# SCH_Manip_2024-04-15.net
KiCad netlist of a schematic drawn in EasyEDA
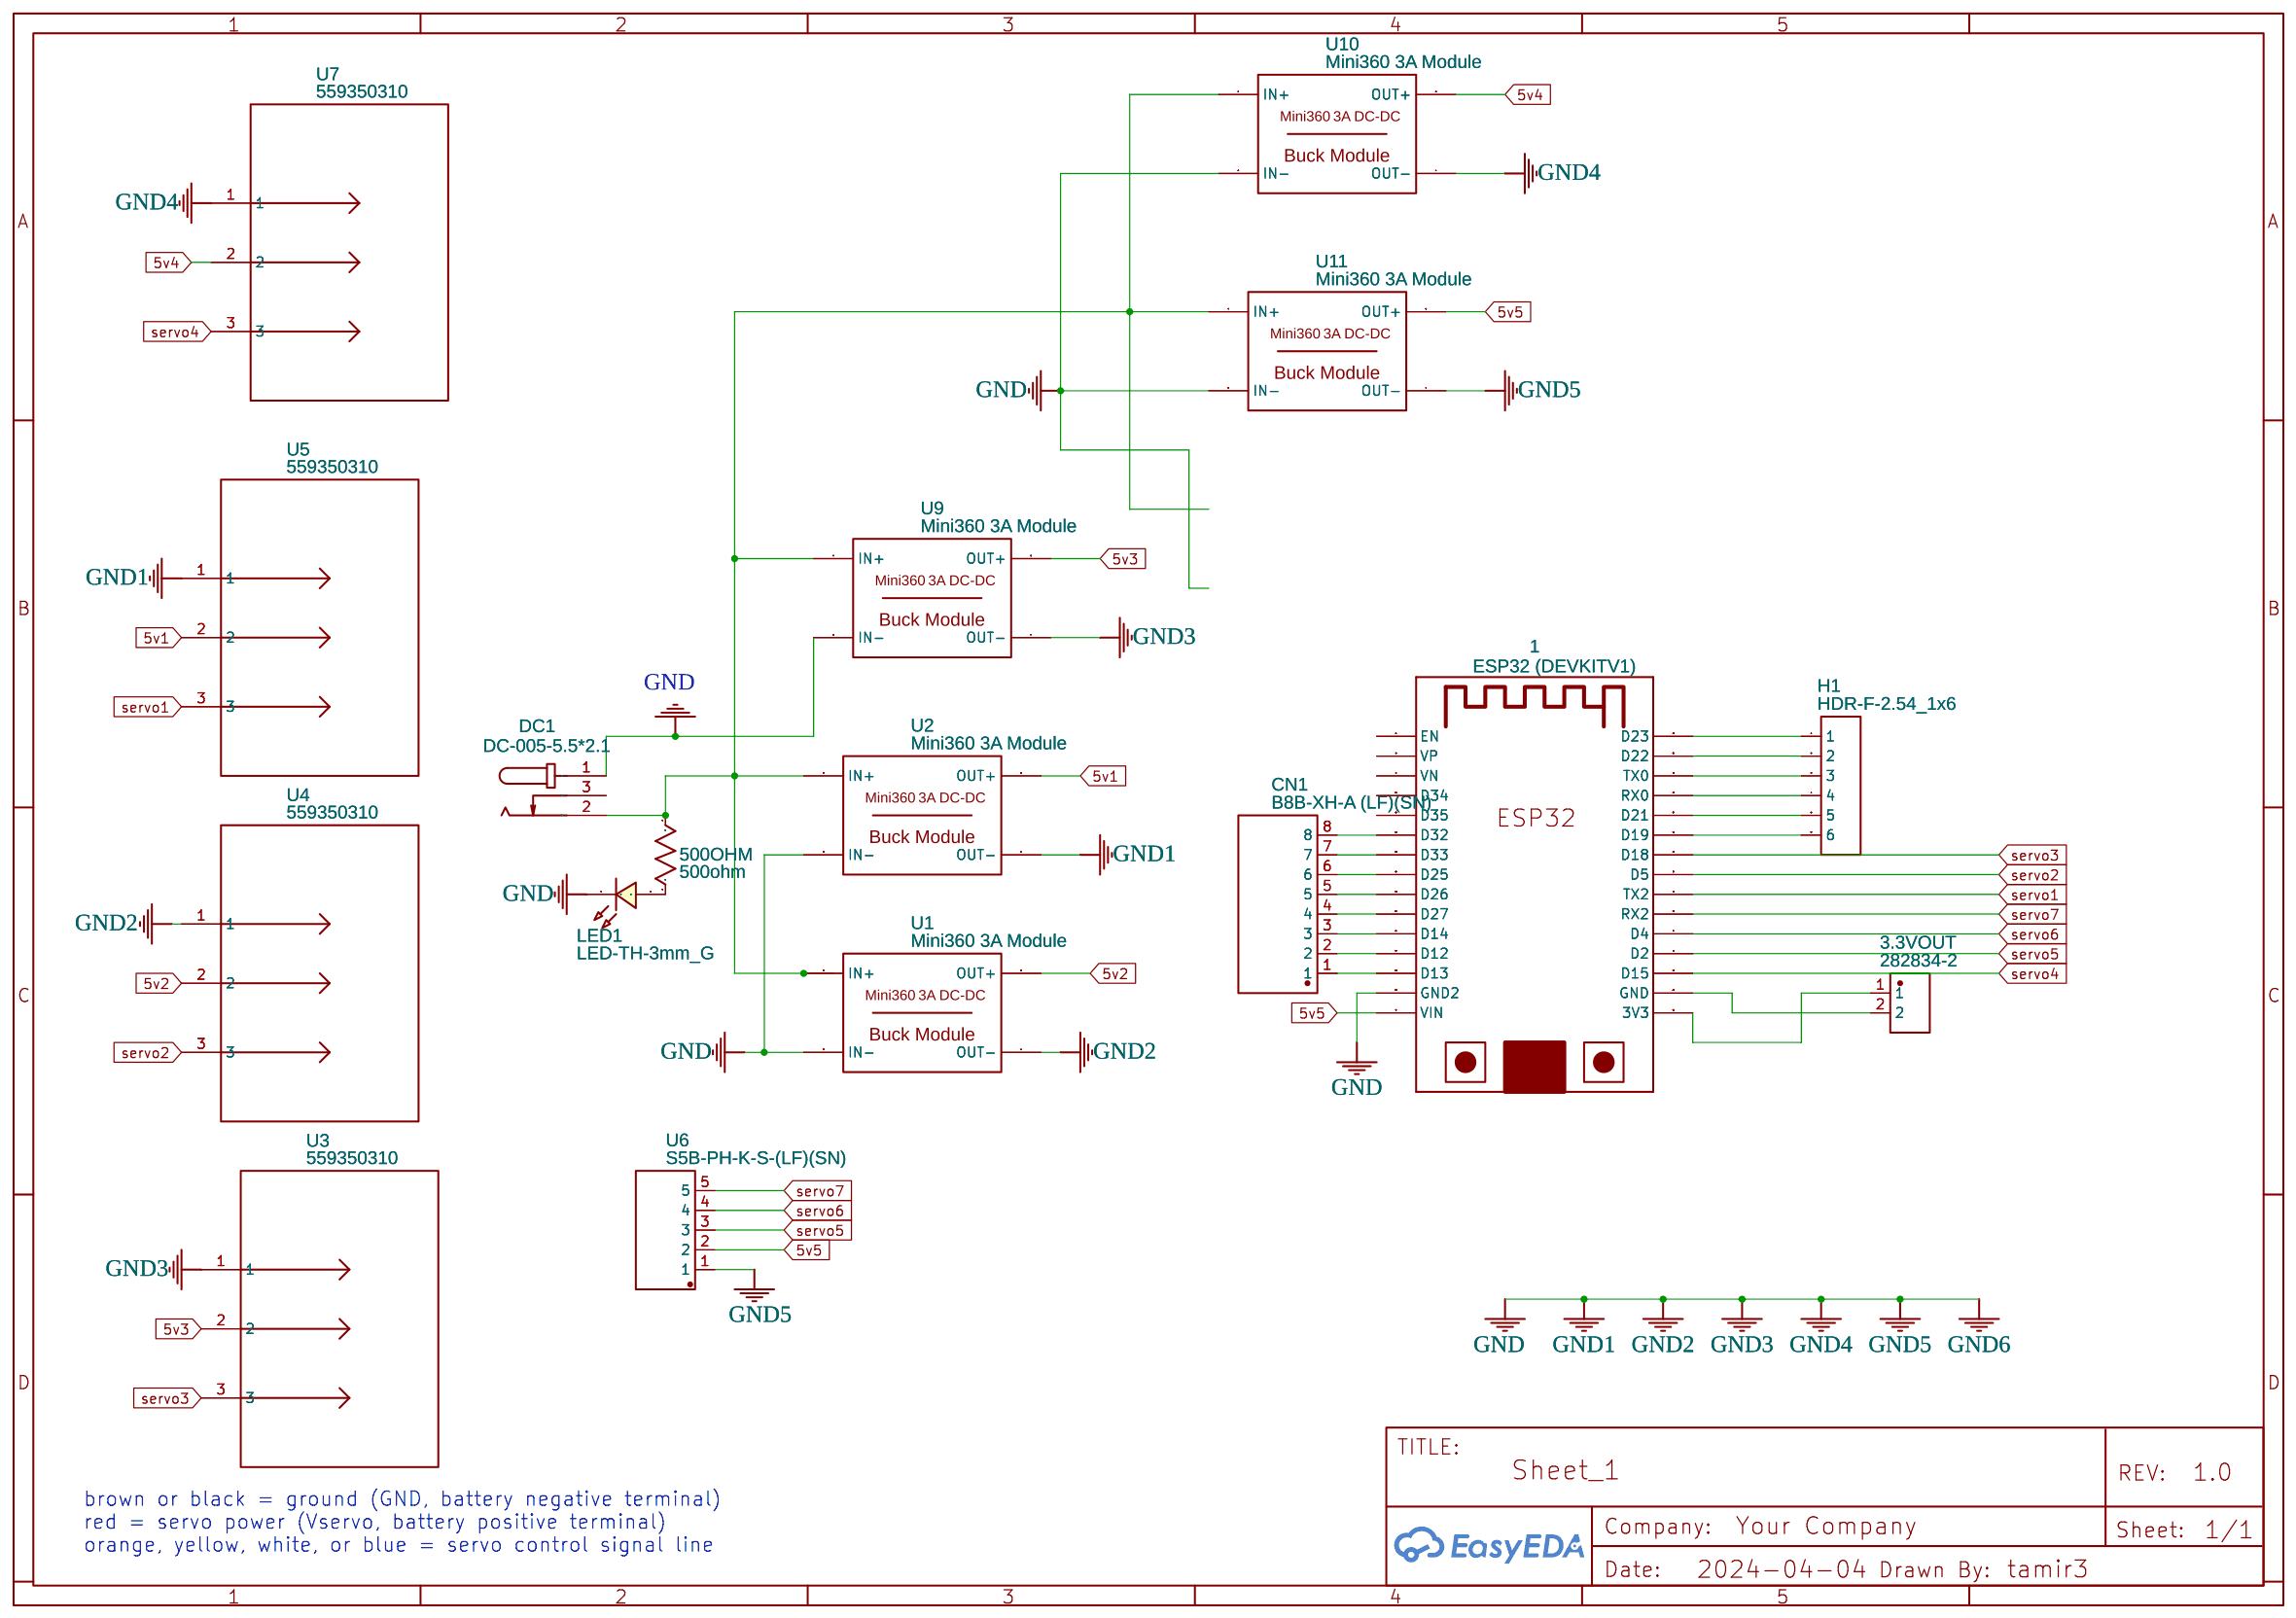
[diagram p0: schematic sheet]

(export (version "E")
  (design (tool "Eeschema 10.0.6"))
  (components
    (comp (ref "1") (value "ESP32 (DEVKITV1)") (libsource (lib "") (part "ESP32-DEVKIT-V1-30PIN")))
    (comp (ref "3.3VOUT")
      (value "282834-2")
      (fields (field (name "Manufacturer") "TE Connectivity(泰科电子)"))
      (libsource (lib "") (part "282834-2"))
    )
    (comp (ref "500OHM") (value "500ohm") (libsource (lib "") (part "R_AXIAL-0.6_US")))
    (comp (ref "CN1")
      (value "B8B-XH-A (LF)(SN)")
      (fields (field (name "Manufacturer Part") "B8B-XH-A(LF)(SN)") (field (name "Manufacturer") "JST"))
      (libsource (lib "") (part "B8B-XH-A (LF)(SN)"))
    )
    (comp (ref "DC1") (value "DC-005-5.5*2.1") (libsource (lib "") (part "DC-005-5.5*2.1")))
    (comp (ref "H1") (value "HDR-F-2.54_1x6") (libsource (lib "") (part "HDR-F-2.54_1x6")))
    (comp (ref "LED1")
      (value "LED-TH-3mm_G")
      (fields
        (field (name "Manufacturer Part") "204-10SYGD/S530-E3")
        (field (name "Manufacturer") "EVERLIGHT(台湾亿光)")
      )
      (libsource (lib "") (part "LED-TH-3mm_G"))
    )
    (comp (ref "U1") (value "Mini360 3A Module") (libsource (lib "") (part "Mini360 3A Module")))
    (comp (ref "U2") (value "Mini360 3A Module") (libsource (lib "") (part "Mini360 3A Module")))
    (comp (ref "U3")
      (value "559350310")
      (fields (field (name "Manufacturer") "MOLEX"))
      (libsource (lib "") (part "559350310"))
    )
    (comp (ref "U4")
      (value "559350310")
      (fields (field (name "Manufacturer") "MOLEX"))
      (libsource (lib "") (part "559350310"))
    )
    (comp (ref "U5")
      (value "559350310")
      (fields (field (name "Manufacturer") "MOLEX"))
      (libsource (lib "") (part "559350310"))
    )
    (comp (ref "U6")
      (value "S5B-PH-K-S-(LF)(SN)")
      (fields (field (name "Manufacturer Part") "S5B-PH-K-S(LF)(SN)") (field (name "Manufacturer") "JST"))
      (libsource (lib "") (part "S5B-PH-K-S-(LF)(SN)"))
    )
    (comp (ref "U7")
      (value "559350310")
      (fields (field (name "Manufacturer") "MOLEX"))
      (libsource (lib "") (part "559350310"))
    )
    (comp (ref "U9") (value "Mini360 3A Module") (libsource (lib "") (part "Mini360 3A Module")))
    (comp (ref "U10") (value "Mini360 3A Module") (libsource (lib "") (part "Mini360 3A Module")))
    (comp (ref "U11") (value "Mini360 3A Module") (libsource (lib "") (part "Mini360 3A Module")))
  )
  (nets
    (net (code "1") (name "5v1") (class "Default")
      (node (ref "U2") (pin "3") (pinfunction "OUT+_3") (pintype "unspecified"))
      (node (ref "U5") (pin "2") (pinfunction "2_2") (pintype "unspecified"))
    )
    (net (code "2") (name "5v2") (class "Default")
      (node (ref "U1") (pin "3") (pinfunction "OUT+_3") (pintype "unspecified"))
      (node (ref "U4") (pin "2") (pinfunction "2_2") (pintype "unspecified"))
    )
    (net (code "3") (name "5v3") (class "Default")
      (node (ref "U3") (pin "2") (pinfunction "2_2") (pintype "unspecified"))
      (node (ref "U9") (pin "3") (pinfunction "OUT+_3") (pintype "unspecified"))
    )
    (net (code "4") (name "5v4") (class "Default")
      (node (ref "U10") (pin "3") (pinfunction "OUT+_3") (pintype "unspecified"))
      (node (ref "U7") (pin "2") (pinfunction "2_2") (pintype "unspecified"))
    )
    (net (code "5") (name "5v5") (class "Default")
      (node (ref "1") (pin "VIN") (pinfunction "VIN_VIN") (pintype "unspecified"))
      (node (ref "U11") (pin "3") (pinfunction "OUT+_3") (pintype "unspecified"))
      (node (ref "U6") (pin "2") (pinfunction "2_2") (pintype "unspecified"))
    )
    (net (code "6") (name "GND") (class "Default")
      (node (ref "1") (pin "GND2") (pinfunction "GND2_GND2") (pintype "unspecified"))
      (node (ref "DC1") (pin "1") (pinfunction "1_1") (pintype "unspecified"))
      (node (ref "LED1") (pin "2") (pinfunction "2_2") (pintype "unspecified"))
      (node (ref "U1") (pin "2") (pinfunction "IN-_2") (pintype "unspecified"))
      (node (ref "U1") (pin "4") (pinfunction "OUT-_4") (pintype "unspecified"))
      (node (ref "U10") (pin "2") (pinfunction "IN-_2") (pintype "unspecified"))
      (node (ref "U10") (pin "4") (pinfunction "OUT-_4") (pintype "unspecified"))
      (node (ref "U11") (pin "2") (pinfunction "IN-_2") (pintype "unspecified"))
      (node (ref "U11") (pin "4") (pinfunction "OUT-_4") (pintype "unspecified"))
      (node (ref "U2") (pin "2") (pinfunction "IN-_2") (pintype "unspecified"))
      (node (ref "U2") (pin "4") (pinfunction "OUT-_4") (pintype "unspecified"))
      (node (ref "U3") (pin "1") (pinfunction "1_1") (pintype "unspecified"))
      (node (ref "U4") (pin "1") (pinfunction "1_1") (pintype "unspecified"))
      (node (ref "U5") (pin "1") (pinfunction "1_1") (pintype "unspecified"))
      (node (ref "U6") (pin "1") (pinfunction "1_1") (pintype "unspecified"))
      (node (ref "U7") (pin "1") (pinfunction "1_1") (pintype "unspecified"))
      (node (ref "U9") (pin "2") (pinfunction "IN-_2") (pintype "unspecified"))
      (node (ref "U9") (pin "4") (pinfunction "OUT-_4") (pintype "unspecified"))
    )
    (net (code "7") (name "Net-(1-Pad3V3)") (class "Default")
      (node (ref "1") (pin "3V3") (pinfunction "3V3_3V3") (pintype "unspecified"))
      (node (ref "3.3VOUT") (pin "1") (pinfunction "1_1") (pintype "unspecified"))
    )
    (net (code "8") (name "Net-(1-PadD12)") (class "Default")
      (node (ref "1") (pin "D12") (pinfunction "D12_D12") (pintype "unspecified"))
      (node (ref "CN1") (pin "2") (pinfunction "2_2") (pintype "unspecified"))
    )
    (net (code "9") (name "Net-(1-PadD13)") (class "Default")
      (node (ref "1") (pin "D13") (pinfunction "D13_D13") (pintype "unspecified"))
      (node (ref "CN1") (pin "1") (pinfunction "1_1") (pintype "unspecified"))
    )
    (net (code "10") (name "Net-(1-PadD14)") (class "Default")
      (node (ref "1") (pin "D14") (pinfunction "D14_D14") (pintype "unspecified"))
      (node (ref "CN1") (pin "3") (pinfunction "3_3") (pintype "unspecified"))
    )
    (net (code "11") (name "Net-(1-PadD19)") (class "Default")
      (node (ref "1") (pin "D19") (pinfunction "D19_D19") (pintype "unspecified"))
      (node (ref "H1") (pin "6") (pinfunction "6_6") (pintype "input"))
    )
    (net (code "12") (name "Net-(1-PadD21)") (class "Default")
      (node (ref "1") (pin "D21") (pinfunction "D21_D21") (pintype "unspecified"))
      (node (ref "H1") (pin "5") (pinfunction "5_5") (pintype "input"))
    )
    (net (code "13") (name "Net-(1-PadD22)") (class "Default")
      (node (ref "1") (pin "D22") (pinfunction "D22_D22") (pintype "unspecified"))
      (node (ref "H1") (pin "2") (pinfunction "2_2") (pintype "input"))
    )
    (net (code "14") (name "Net-(1-PadD23)") (class "Default")
      (node (ref "1") (pin "D23") (pinfunction "D23_D23") (pintype "unspecified"))
      (node (ref "H1") (pin "1") (pinfunction "1_1") (pintype "input"))
    )
    (net (code "15") (name "Net-(1-PadD25)") (class "Default")
      (node (ref "1") (pin "D25") (pinfunction "D25_D25") (pintype "unspecified"))
      (node (ref "CN1") (pin "6") (pinfunction "6_6") (pintype "unspecified"))
    )
    (net (code "16") (name "Net-(1-PadD26)") (class "Default")
      (node (ref "1") (pin "D26") (pinfunction "D26_D26") (pintype "unspecified"))
      (node (ref "CN1") (pin "5") (pinfunction "5_5") (pintype "unspecified"))
    )
    (net (code "17") (name "Net-(1-PadD27)") (class "Default")
      (node (ref "1") (pin "D27") (pinfunction "D27_D27") (pintype "unspecified"))
      (node (ref "CN1") (pin "4") (pinfunction "4_4") (pintype "unspecified"))
    )
    (net (code "18") (name "Net-(1-PadD32)") (class "Default")
      (node (ref "1") (pin "D32") (pinfunction "D32_D32") (pintype "unspecified"))
      (node (ref "CN1") (pin "8") (pinfunction "8_8") (pintype "unspecified"))
    )
    (net (code "19") (name "Net-(1-PadD33)") (class "Default")
      (node (ref "1") (pin "D33") (pinfunction "D33_D33") (pintype "unspecified"))
      (node (ref "CN1") (pin "7") (pinfunction "7_7") (pintype "unspecified"))
    )
    (net (code "20") (name "Net-(1-PadGND)") (class "Default")
      (node (ref "1") (pin "GND") (pinfunction "GND_GND") (pintype "unspecified"))
      (node (ref "3.3VOUT") (pin "2") (pinfunction "2_2") (pintype "unspecified"))
    )
    (net (code "21") (name "Net-(1-PadRX0)") (class "Default")
      (node (ref "1") (pin "RX0") (pinfunction "RX0_RX0") (pintype "unspecified"))
      (node (ref "H1") (pin "4") (pinfunction "4_4") (pintype "input"))
    )
    (net (code "22") (name "Net-(1-PadTX0)") (class "Default")
      (node (ref "1") (pin "TX0") (pinfunction "TX0_TX0") (pintype "unspecified"))
      (node (ref "H1") (pin "3") (pinfunction "3_3") (pintype "input"))
    )
    (net (code "23") (name "Net-(500OHM-Pad1)") (class "Default")
      (node (ref "500OHM") (pin "1") (pinfunction "1_1") (pintype "unspecified"))
      (node (ref "LED1") (pin "1") (pinfunction "1_1") (pintype "unspecified"))
    )
    (net (code "24") (name "Net-(U1-IN+)") (class "Default")
      (node (ref "500OHM") (pin "2") (pinfunction "2_2") (pintype "unspecified"))
      (node (ref "DC1") (pin "2") (pinfunction "2_2") (pintype "unspecified"))
      (node (ref "U1") (pin "1") (pinfunction "IN+_1") (pintype "unspecified"))
      (node (ref "U10") (pin "1") (pinfunction "IN+_1") (pintype "unspecified"))
      (node (ref "U11") (pin "1") (pinfunction "IN+_1") (pintype "unspecified"))
      (node (ref "U2") (pin "1") (pinfunction "IN+_1") (pintype "unspecified"))
      (node (ref "U9") (pin "1") (pinfunction "IN+_1") (pintype "unspecified"))
    )
    (net (code "25") (name "servo1") (class "Default")
      (node (ref "1") (pin "TX2") (pinfunction "TX2_TX2") (pintype "unspecified"))
      (node (ref "U5") (pin "3") (pinfunction "3_3") (pintype "unspecified"))
    )
    (net (code "26") (name "servo2") (class "Default")
      (node (ref "1") (pin "D5") (pinfunction "D5_D5") (pintype "unspecified"))
      (node (ref "U4") (pin "3") (pinfunction "3_3") (pintype "unspecified"))
    )
    (net (code "27") (name "servo3") (class "Default")
      (node (ref "1") (pin "D18") (pinfunction "D18_D18") (pintype "unspecified"))
      (node (ref "U3") (pin "3") (pinfunction "3_3") (pintype "unspecified"))
    )
    (net (code "28") (name "servo4") (class "Default")
      (node (ref "1") (pin "D15") (pinfunction "D15_D15") (pintype "unspecified"))
      (node (ref "U7") (pin "3") (pinfunction "3_3") (pintype "unspecified"))
    )
    (net (code "29") (name "servo5") (class "Default")
      (node (ref "1") (pin "D2") (pinfunction "D2_D2") (pintype "unspecified"))
      (node (ref "U6") (pin "3") (pinfunction "3_3") (pintype "unspecified"))
    )
    (net (code "30") (name "servo6") (class "Default")
      (node (ref "1") (pin "D4") (pinfunction "D4_D4") (pintype "unspecified"))
      (node (ref "U6") (pin "4") (pinfunction "4_4") (pintype "unspecified"))
    )
    (net (code "31") (name "servo7") (class "Default")
      (node (ref "1") (pin "RX2") (pinfunction "RX2_RX2") (pintype "unspecified"))
      (node (ref "U6") (pin "5") (pinfunction "5_5") (pintype "unspecified"))
    )
    (net (code "32") (name "unconnected-(1-PadD34)") (class "Default")
      (node (ref "1") (pin "D34") (pinfunction "D34_D34") (pintype "unspecified"))
    )
    (net (code "33") (name "unconnected-(1-PadD35)") (class "Default")
      (node (ref "1") (pin "D35") (pinfunction "D35_D35") (pintype "unspecified"))
    )
    (net (code "34") (name "unconnected-(1-PadEN)") (class "Default")
      (node (ref "1") (pin "EN") (pinfunction "EN_EN") (pintype "unspecified"))
    )
    (net (code "35") (name "unconnected-(1-PadVN)") (class "Default")
      (node (ref "1") (pin "VN") (pinfunction "VN_VN") (pintype "unspecified"))
    )
    (net (code "36") (name "unconnected-(1-PadVP)") (class "Default")
      (node (ref "1") (pin "VP") (pinfunction "VP_VP") (pintype "unspecified"))
    )
    (net (code "37") (name "unconnected-(DC1-Pad3)") (class "Default")
      (node (ref "DC1") (pin "3") (pinfunction "3_3") (pintype "unspecified"))
    )
  )
)
